# DigitalInterfaces.net
KiCad netlist of a schematic drawn in Altium Designer
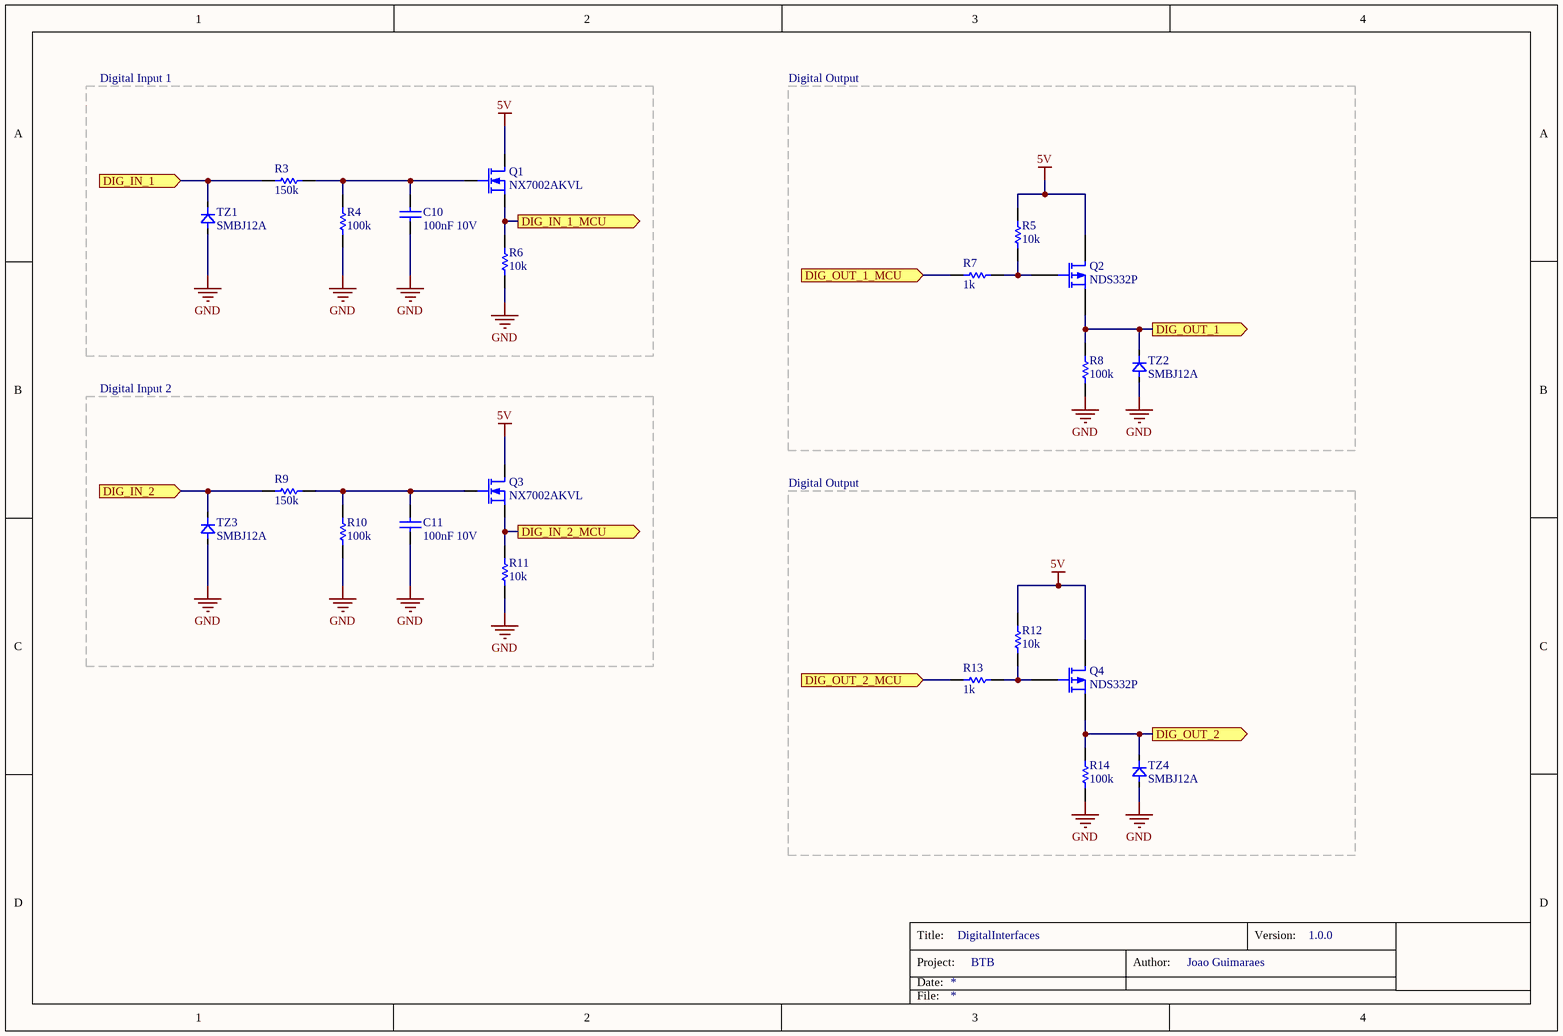
[diagram p0: DigitalInterfaces.SchDoc]

(export (version "E")
  (design (tool "Eeschema 10.0.6"))
  (components
    (comp (ref "C10")
      (value "100nF 10V")
      (footprint "0402")
      (description "Capacitor")
      (fields (field (name "PARTNUMBER") "CAP.100n.10V.20%.SMD.0402") (field (name "MANUFACTURER") "Wurth"))
      (libsource (lib "IntLib") (part "Cap"))
    )
    (comp (ref "C11")
      (value "100nF 10V")
      (footprint "0402")
      (description "Capacitor")
      (fields (field (name "PARTNUMBER") "CAP.100n.10V.20%.SMD.0402") (field (name "MANUFACTURER") "Wurth"))
      (libsource (lib "IntLib") (part "Cap"))
    )
    (comp (ref "Q1")
      (value "NX7002AKVL")
      (footprint "SOT23_M")
      (description "Small Signal MOSFET 60 V, 310 mA, Single, N−Channel, SOT−23")
      (fields (field (name "MANUFACTURER") "Nexperia"))
      (libsource (lib "IntLib") (part "NX7002AKVL"))
    )
    (comp (ref "Q2")
      (value "NDS332P")
      (footprint "SOT23_M")
      (description "P-Channel Logic Level Enhancement MOSFET")
      (libsource (lib "IntLib") (part "NDS332P"))
    )
    (comp (ref "Q3")
      (value "NX7002AKVL")
      (footprint "SOT23_M")
      (description "Small Signal MOSFET 60 V, 310 mA, Single, N−Channel, SOT−23")
      (fields (field (name "MANUFACTURER") "Nexperia"))
      (libsource (lib "IntLib") (part "NX7002AKVL"))
    )
    (comp (ref "Q4")
      (value "NDS332P")
      (footprint "SOT23_M")
      (description "P-Channel Logic Level Enhancement MOSFET")
      (fields (field (name "MANUFACTURER") "ON Semiconductor"))
      (libsource (lib "IntLib") (part "NDS332P"))
    )
    (comp (ref "R3")
      (value "150k")
      (footprint "6-0805_M")
      (description "Resistor")
      (fields (field (name "PARTNUMBER") "RES.150K.1/8W.5%.SMD.0805") (field (name "MANUFACTURER") "Vishay"))
      (libsource (lib "IntLib") (part "Res"))
    )
    (comp (ref "R4")
      (value "100k")
      (footprint "6-0805_M")
      (description "Resistor")
      (fields (field (name "PARTNUMBER") "RES.100K.1/8W.5%.SMD.0805") (field (name "MANUFACTURER") "Vishay"))
      (libsource (lib "IntLib") (part "Res"))
    )
    (comp (ref "R5")
      (value "10k")
      (footprint "6-0805_M")
      (description "Resistor")
      (fields (field (name "PARTNUMBER") "RES.10K.1/8W.5%.SMD.0805") (field (name "MANUFACTURER") "Yageo"))
      (libsource (lib "IntLib") (part "Res"))
    )
    (comp (ref "R6")
      (value "10k")
      (footprint "6-0805_M")
      (description "Resistor")
      (fields (field (name "PARTNUMBER") "RES.10K.1/8W.5%.SMD.0805") (field (name "MANUFACTURER") "Yageo"))
      (libsource (lib "IntLib") (part "Res"))
    )
    (comp (ref "R7")
      (value "1k")
      (footprint "6-0805_M")
      (description "Resistor")
      (fields (field (name "PARTNUMBER") "RES.1K.1/8W.5%.SMD.0805") (field (name "MANUFACTURER") "Yageo"))
      (libsource (lib "IntLib") (part "Res"))
    )
    (comp (ref "R8")
      (value "100k")
      (footprint "6-0805_M")
      (description "Resistor")
      (fields (field (name "PARTNUMBER") "RES.100K.1/8W.5%.SMD.0805") (field (name "MANUFACTURER") "Vishay"))
      (libsource (lib "IntLib") (part "Res"))
    )
    (comp (ref "R9")
      (value "150k")
      (footprint "6-0805_M")
      (description "Resistor")
      (fields (field (name "PARTNUMBER") "RES.150K.1/8W.5%.SMD.0805") (field (name "MANUFACTURER") "Vishay"))
      (libsource (lib "IntLib") (part "Res"))
    )
    (comp (ref "R10")
      (value "100k")
      (footprint "6-0805_M")
      (description "Resistor")
      (fields (field (name "PARTNUMBER") "RES.100K.1/8W.5%.SMD.0805") (field (name "MANUFACTURER") "Vishay"))
      (libsource (lib "IntLib") (part "Res"))
    )
    (comp (ref "R11")
      (value "10k")
      (footprint "6-0805_M")
      (description "Resistor")
      (fields (field (name "PARTNUMBER") "RES.10K.1/8W.5%.SMD.0805") (field (name "MANUFACTURER") "Yageo"))
      (libsource (lib "IntLib") (part "Res"))
    )
    (comp (ref "R12")
      (value "10k")
      (footprint "6-0805_M")
      (description "Resistor")
      (fields (field (name "PARTNUMBER") "RES.100K.1/8W.5%.SMD.0805") (field (name "MANUFACTURER") "Vishay"))
      (libsource (lib "IntLib") (part "Res"))
    )
    (comp (ref "R13")
      (value "1k")
      (footprint "6-0805_M")
      (description "Resistor")
      (fields (field (name "PARTNUMBER") "RES.1K.1/8W.5%.SMD.0805") (field (name "MANUFACTURER") "Yageo"))
      (libsource (lib "IntLib") (part "Res"))
    )
    (comp (ref "R14")
      (value "100k")
      (footprint "6-0805_M")
      (description "Resistor")
      (fields (field (name "PARTNUMBER") "RES.100K.1/8W.5%.SMD.0805") (field (name "MANUFACTURER") "Vishay"))
      (libsource (lib "IntLib") (part "Res"))
    )
    (comp (ref "TZ1")
      (value "SMBJ12A")
      (footprint "DO-214AA")
      (description "ESD Suppressors / TVS Diodes 12V 600W SMB Unidirectional")
      (fields (field (name "MANUFACTURER") "ON Semiconductor"))
      (libsource (lib "IntLib") (part "SMBJ12A"))
    )
    (comp (ref "TZ2")
      (value "SMBJ12A")
      (footprint "DO-214AA")
      (description "ESD Suppressors / TVS Diodes 12V 600W SMB Unidirectional")
      (fields (field (name "MANUFACTURER") "ON Semiconductor"))
      (libsource (lib "IntLib") (part "SMBJ12A"))
    )
    (comp (ref "TZ3")
      (value "SMBJ12A")
      (footprint "DO-214AA")
      (description "ESD Suppressors / TVS Diodes 12V 600W SMB Unidirectional")
      (fields (field (name "MANUFACTURER") "ON Semiconductor"))
      (libsource (lib "IntLib") (part "SMBJ12A"))
    )
    (comp (ref "TZ4")
      (value "SMBJ12A")
      (footprint "DO-214AA")
      (description "ESD Suppressors / TVS Diodes 12V 600W SMB Unidirectional")
      (fields (field (name "MANUFACTURER") "ON Semiconductor"))
      (libsource (lib "IntLib") (part "SMBJ12A"))
    )
  )
  (nets
    (net (code "1") (name "/DIG_IN_1") (class "Default")
      (node (ref "R3") (pin "1") (pinfunction "1_1") (pintype "passive"))
      (node (ref "TZ1") (pin "2") (pinfunction "C_2") (pintype "passive"))
    )
    (net (code "2") (name "/DIG_IN_1_MCU") (class "Default")
      (node (ref "Q1") (pin "2") (pinfunction "S_2") (pintype "passive"))
      (node (ref "R6") (pin "2") (pinfunction "2_2") (pintype "passive"))
    )
    (net (code "3") (name "/DIG_IN_2") (class "Default")
      (node (ref "R9") (pin "1") (pinfunction "1_1") (pintype "passive"))
      (node (ref "TZ3") (pin "2") (pinfunction "C_2") (pintype "passive"))
    )
    (net (code "4") (name "/DIG_IN_2_MCU") (class "Default")
      (node (ref "Q3") (pin "2") (pinfunction "S_2") (pintype "passive"))
      (node (ref "R11") (pin "2") (pinfunction "2_2") (pintype "passive"))
    )
    (net (code "5") (name "/DIG_OUT_1") (class "Default")
      (node (ref "Q2") (pin "2") (pinfunction "S_2") (pintype "passive"))
      (node (ref "R8") (pin "2") (pinfunction "2_2") (pintype "passive"))
      (node (ref "TZ2") (pin "2") (pinfunction "C_2") (pintype "passive"))
    )
    (net (code "6") (name "/DIG_OUT_1_MCU") (class "Default")
      (node (ref "R7") (pin "1") (pinfunction "1_1") (pintype "passive"))
    )
    (net (code "7") (name "/DIG_OUT_2") (class "Default")
      (node (ref "Q4") (pin "2") (pinfunction "S_2") (pintype "passive"))
      (node (ref "R14") (pin "2") (pinfunction "2_2") (pintype "passive"))
      (node (ref "TZ4") (pin "2") (pinfunction "C_2") (pintype "passive"))
    )
    (net (code "8") (name "/DIG_OUT_2_MCU") (class "Default")
      (node (ref "R13") (pin "1") (pinfunction "1_1") (pintype "passive"))
    )
    (net (code "9") (name "5V") (class "Default")
      (node (ref "Q1") (pin "3") (pinfunction "D_3") (pintype "passive"))
      (node (ref "Q2") (pin "1") (pinfunction "D_1") (pintype "passive"))
      (node (ref "Q3") (pin "3") (pinfunction "D_3") (pintype "passive"))
      (node (ref "Q4") (pin "1") (pinfunction "D_1") (pintype "passive"))
      (node (ref "R12") (pin "2") (pinfunction "2_2") (pintype "passive"))
      (node (ref "R5") (pin "2") (pinfunction "2_2") (pintype "passive"))
    )
    (net (code "10") (name "GND") (class "Default")
      (node (ref "C10") (pin "1") (pinfunction "1_1") (pintype "passive"))
      (node (ref "C11") (pin "1") (pinfunction "1_1") (pintype "passive"))
      (node (ref "R10") (pin "1") (pinfunction "1_1") (pintype "passive"))
      (node (ref "R11") (pin "1") (pinfunction "1_1") (pintype "passive"))
      (node (ref "R14") (pin "1") (pinfunction "1_1") (pintype "passive"))
      (node (ref "R4") (pin "1") (pinfunction "1_1") (pintype "passive"))
      (node (ref "R6") (pin "1") (pinfunction "1_1") (pintype "passive"))
      (node (ref "R8") (pin "1") (pinfunction "1_1") (pintype "passive"))
      (node (ref "TZ1") (pin "1") (pinfunction "A_1") (pintype "passive"))
      (node (ref "TZ2") (pin "1") (pinfunction "A_1") (pintype "passive"))
      (node (ref "TZ3") (pin "1") (pinfunction "A_1") (pintype "passive"))
      (node (ref "TZ4") (pin "1") (pinfunction "A_1") (pintype "passive"))
    )
    (net (code "11") (name "Net-(Q1-G)") (class "Default")
      (node (ref "C10") (pin "2") (pinfunction "2_2") (pintype "passive"))
      (node (ref "Q1") (pin "1") (pinfunction "G_1") (pintype "passive"))
      (node (ref "R3") (pin "2") (pinfunction "2_2") (pintype "passive"))
      (node (ref "R4") (pin "2") (pinfunction "2_2") (pintype "passive"))
    )
    (net (code "12") (name "Net-(Q2-G)") (class "Default")
      (node (ref "Q2") (pin "3") (pinfunction "G_3") (pintype "passive"))
      (node (ref "R5") (pin "1") (pinfunction "1_1") (pintype "passive"))
      (node (ref "R7") (pin "2") (pinfunction "2_2") (pintype "passive"))
    )
    (net (code "13") (name "Net-(Q3-G)") (class "Default")
      (node (ref "C11") (pin "2") (pinfunction "2_2") (pintype "passive"))
      (node (ref "Q3") (pin "1") (pinfunction "G_1") (pintype "passive"))
      (node (ref "R10") (pin "2") (pinfunction "2_2") (pintype "passive"))
      (node (ref "R9") (pin "2") (pinfunction "2_2") (pintype "passive"))
    )
    (net (code "14") (name "Net-(Q4-G)") (class "Default")
      (node (ref "Q4") (pin "3") (pinfunction "G_3") (pintype "passive"))
      (node (ref "R12") (pin "1") (pinfunction "1_1") (pintype "passive"))
      (node (ref "R13") (pin "2") (pinfunction "2_2") (pintype "passive"))
    )
  )
)
